# R107.net
KiCad netlist of a schematic drawn in EAGLE
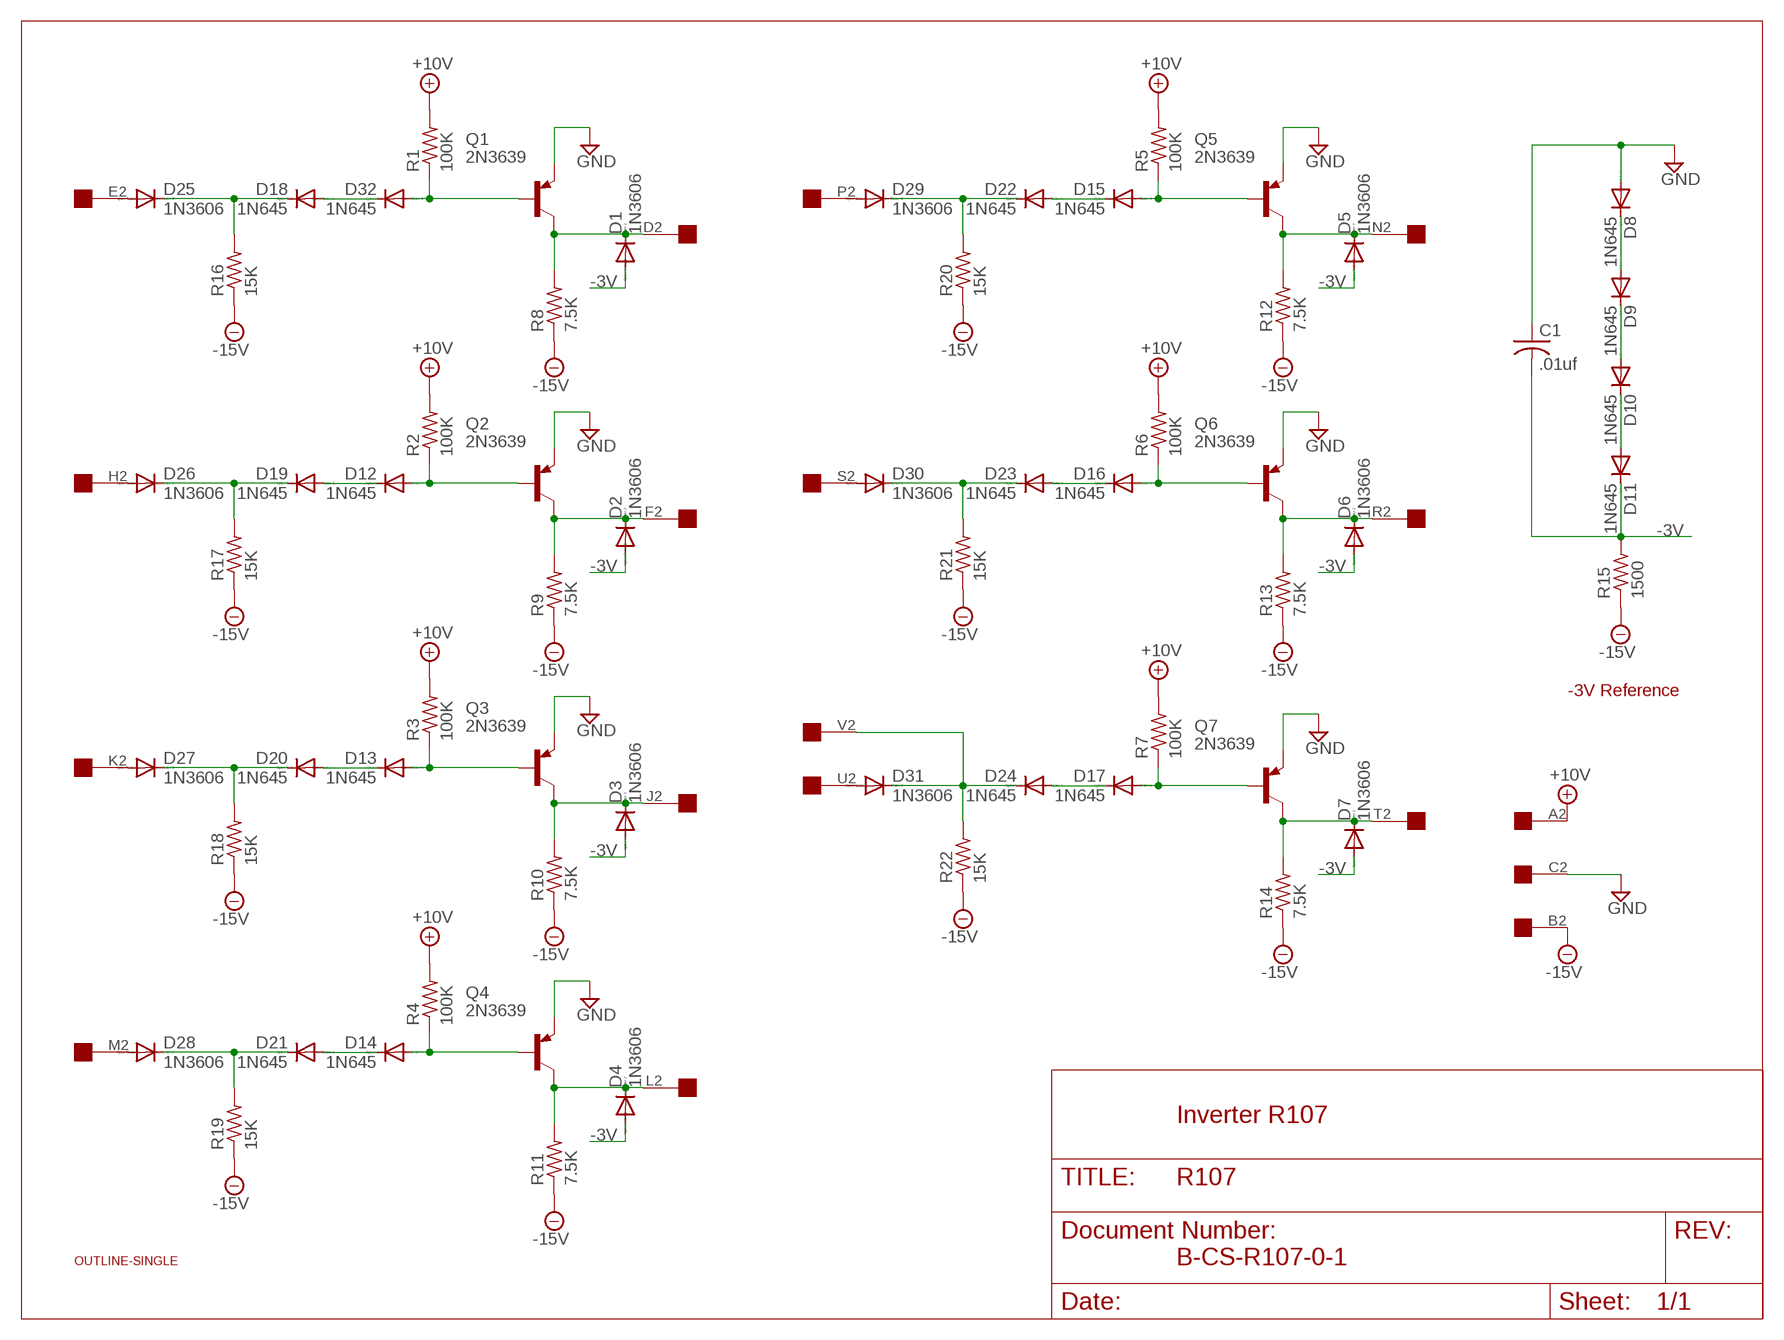
[diagram p0: schematic, sheet 1]

(export (version "E")
  (design (tool "Eeschema 10.0.6"))
  (components
    (comp (ref "C1")
      (value ".01uf")
      (footprint "eagle-import:C050-025X075")
      (libsource (lib "eagle-import") (part "C-US050-025X075"))
    )
    (comp (ref "D1")
      (value "1N3606")
      (footprint "eagle-import:DO35-10")
      (libsource (lib "eagle-import") (part "1N4148DO35-10"))
    )
    (comp (ref "D2")
      (value "1N3606")
      (footprint "eagle-import:DO35-10")
      (libsource (lib "eagle-import") (part "1N4148DO35-10"))
    )
    (comp (ref "D3")
      (value "1N3606")
      (footprint "eagle-import:DO35-10")
      (libsource (lib "eagle-import") (part "1N4148DO35-10"))
    )
    (comp (ref "D4")
      (value "1N3606")
      (footprint "eagle-import:DO35-10")
      (libsource (lib "eagle-import") (part "1N4148DO35-10"))
    )
    (comp (ref "D5")
      (value "1N3606")
      (footprint "eagle-import:DO35-10")
      (libsource (lib "eagle-import") (part "1N4148DO35-10"))
    )
    (comp (ref "D6")
      (value "1N3606")
      (footprint "eagle-import:DO35-10")
      (libsource (lib "eagle-import") (part "1N4148DO35-10"))
    )
    (comp (ref "D7")
      (value "1N3606")
      (footprint "eagle-import:DO35-10")
      (libsource (lib "eagle-import") (part "1N4148DO35-10"))
    )
    (comp (ref "D8")
      (value "1N645")
      (footprint "eagle-import:DO35-10")
      (libsource (lib "eagle-import") (part "1N4148DO35-10"))
    )
    (comp (ref "D9")
      (value "1N645")
      (footprint "eagle-import:DO35-10")
      (libsource (lib "eagle-import") (part "1N4148DO35-10"))
    )
    (comp (ref "D10")
      (value "1N645")
      (footprint "eagle-import:DO35-10")
      (libsource (lib "eagle-import") (part "1N4148DO35-10"))
    )
    (comp (ref "D11")
      (value "1N645")
      (footprint "eagle-import:DO35-10")
      (libsource (lib "eagle-import") (part "1N4148DO35-10"))
    )
    (comp (ref "D12")
      (value "1N645")
      (footprint "eagle-import:DO35-10")
      (libsource (lib "eagle-import") (part "1N4148DO35-10"))
    )
    (comp (ref "D13")
      (value "1N645")
      (footprint "eagle-import:DO35-10")
      (libsource (lib "eagle-import") (part "1N4148DO35-10"))
    )
    (comp (ref "D14")
      (value "1N645")
      (footprint "eagle-import:DO35-10")
      (libsource (lib "eagle-import") (part "1N4148DO35-10"))
    )
    (comp (ref "D15")
      (value "1N645")
      (footprint "eagle-import:DO35-10")
      (libsource (lib "eagle-import") (part "1N4148DO35-10"))
    )
    (comp (ref "D16")
      (value "1N645")
      (footprint "eagle-import:DO35-10")
      (libsource (lib "eagle-import") (part "1N4148DO35-10"))
    )
    (comp (ref "D17")
      (value "1N645")
      (footprint "eagle-import:DO35-10")
      (libsource (lib "eagle-import") (part "1N4148DO35-10"))
    )
    (comp (ref "D18")
      (value "1N645")
      (footprint "eagle-import:DO35-10")
      (libsource (lib "eagle-import") (part "1N4148DO35-10"))
    )
    (comp (ref "D19")
      (value "1N645")
      (footprint "eagle-import:DO35-10")
      (libsource (lib "eagle-import") (part "1N4148DO35-10"))
    )
    (comp (ref "D20")
      (value "1N645")
      (footprint "eagle-import:DO35-10")
      (libsource (lib "eagle-import") (part "1N4148DO35-10"))
    )
    (comp (ref "D21")
      (value "1N645")
      (footprint "eagle-import:DO35-10")
      (libsource (lib "eagle-import") (part "1N4148DO35-10"))
    )
    (comp (ref "D22")
      (value "1N645")
      (footprint "eagle-import:DO35-10")
      (libsource (lib "eagle-import") (part "1N4148DO35-10"))
    )
    (comp (ref "D23")
      (value "1N645")
      (footprint "eagle-import:DO35-10")
      (libsource (lib "eagle-import") (part "1N4148DO35-10"))
    )
    (comp (ref "D24")
      (value "1N645")
      (footprint "eagle-import:DO35-10")
      (libsource (lib "eagle-import") (part "1N4148DO35-10"))
    )
    (comp (ref "D25")
      (value "1N3606")
      (footprint "eagle-import:DO35-10")
      (libsource (lib "eagle-import") (part "1N4148DO35-10"))
    )
    (comp (ref "D26")
      (value "1N3606")
      (footprint "eagle-import:DO35-10")
      (libsource (lib "eagle-import") (part "1N4148DO35-10"))
    )
    (comp (ref "D27")
      (value "1N3606")
      (footprint "eagle-import:DO35-10")
      (libsource (lib "eagle-import") (part "1N4148DO35-10"))
    )
    (comp (ref "D28")
      (value "1N3606")
      (footprint "eagle-import:DO35-10")
      (libsource (lib "eagle-import") (part "1N4148DO35-10"))
    )
    (comp (ref "D29")
      (value "1N3606")
      (footprint "eagle-import:DO35-10")
      (libsource (lib "eagle-import") (part "1N4148DO35-10"))
    )
    (comp (ref "D30")
      (value "1N3606")
      (footprint "eagle-import:DO35-10")
      (libsource (lib "eagle-import") (part "1N4148DO35-10"))
    )
    (comp (ref "D31")
      (value "1N3606")
      (footprint "eagle-import:DO35-10")
      (libsource (lib "eagle-import") (part "1N4148DO35-10"))
    )
    (comp (ref "D32")
      (value "1N645")
      (footprint "eagle-import:DO35-10")
      (libsource (lib "eagle-import") (part "1N4148DO35-10"))
    )
    (comp (ref "Q1")
      (value "2N3639")
      (footprint "eagle-import:TO39")
      (libsource (lib "eagle-import") (part "2N3637"))
    )
    (comp (ref "Q2")
      (value "2N3639")
      (footprint "eagle-import:TO39")
      (libsource (lib "eagle-import") (part "2N3637"))
    )
    (comp (ref "Q3")
      (value "2N3639")
      (footprint "eagle-import:TO39")
      (libsource (lib "eagle-import") (part "2N3637"))
    )
    (comp (ref "Q4")
      (value "2N3639")
      (footprint "eagle-import:TO39")
      (libsource (lib "eagle-import") (part "2N3637"))
    )
    (comp (ref "Q5")
      (value "2N3639")
      (footprint "eagle-import:TO39")
      (libsource (lib "eagle-import") (part "2N3637"))
    )
    (comp (ref "Q6")
      (value "2N3639")
      (footprint "eagle-import:TO39")
      (libsource (lib "eagle-import") (part "2N3637"))
    )
    (comp (ref "Q7")
      (value "2N3639")
      (footprint "eagle-import:TO39")
      (libsource (lib "eagle-import") (part "2N3637"))
    )
    (comp (ref "R1")
      (value "100K")
      (footprint "eagle-import:0207_10")
      (libsource (lib "eagle-import") (part "R-US_0207/10"))
    )
    (comp (ref "R2")
      (value "100K")
      (footprint "eagle-import:0207_10")
      (libsource (lib "eagle-import") (part "R-US_0207/10"))
    )
    (comp (ref "R3")
      (value "100K")
      (footprint "eagle-import:0207_10")
      (libsource (lib "eagle-import") (part "R-US_0207/10"))
    )
    (comp (ref "R4")
      (value "100K")
      (footprint "eagle-import:0207_10")
      (libsource (lib "eagle-import") (part "R-US_0207/10"))
    )
    (comp (ref "R5")
      (value "100K")
      (footprint "eagle-import:0207_10")
      (libsource (lib "eagle-import") (part "R-US_0207/10"))
    )
    (comp (ref "R6")
      (value "100K")
      (footprint "eagle-import:0207_10")
      (libsource (lib "eagle-import") (part "R-US_0207/10"))
    )
    (comp (ref "R7")
      (value "100K")
      (footprint "eagle-import:0207_10")
      (libsource (lib "eagle-import") (part "R-US_0207/10"))
    )
    (comp (ref "R8")
      (value "7.5K")
      (footprint "eagle-import:0207_10")
      (libsource (lib "eagle-import") (part "R-US_0207/10"))
    )
    (comp (ref "R9")
      (value "7.5K")
      (footprint "eagle-import:0207_10")
      (libsource (lib "eagle-import") (part "R-US_0207/10"))
    )
    (comp (ref "R10")
      (value "7.5K")
      (footprint "eagle-import:0207_10")
      (libsource (lib "eagle-import") (part "R-US_0207/10"))
    )
    (comp (ref "R11")
      (value "7.5K")
      (footprint "eagle-import:0207_10")
      (libsource (lib "eagle-import") (part "R-US_0207/10"))
    )
    (comp (ref "R12")
      (value "7.5K")
      (footprint "eagle-import:0207_10")
      (libsource (lib "eagle-import") (part "R-US_0207/10"))
    )
    (comp (ref "R13")
      (value "7.5K")
      (footprint "eagle-import:0207_10")
      (libsource (lib "eagle-import") (part "R-US_0207/10"))
    )
    (comp (ref "R14")
      (value "7.5K")
      (footprint "eagle-import:0207_10")
      (libsource (lib "eagle-import") (part "R-US_0207/10"))
    )
    (comp (ref "R15")
      (value "1500")
      (footprint "eagle-import:0207_10")
      (libsource (lib "eagle-import") (part "R-US_0207/10"))
    )
    (comp (ref "R16")
      (value "15K")
      (footprint "eagle-import:0207_10")
      (libsource (lib "eagle-import") (part "R-US_0207/10"))
    )
    (comp (ref "R17")
      (value "15K")
      (footprint "eagle-import:0207_10")
      (libsource (lib "eagle-import") (part "R-US_0207/10"))
    )
    (comp (ref "R18")
      (value "15K")
      (footprint "eagle-import:0207_10")
      (libsource (lib "eagle-import") (part "R-US_0207/10"))
    )
    (comp (ref "R19")
      (value "15K")
      (footprint "eagle-import:0207_10")
      (libsource (lib "eagle-import") (part "R-US_0207/10"))
    )
    (comp (ref "R20")
      (value "15K")
      (footprint "eagle-import:0207_10")
      (libsource (lib "eagle-import") (part "R-US_0207/10"))
    )
    (comp (ref "R21")
      (value "15K")
      (footprint "eagle-import:0207_10")
      (libsource (lib "eagle-import") (part "R-US_0207/10"))
    )
    (comp (ref "R22")
      (value "15K")
      (footprint "eagle-import:0207_10")
      (libsource (lib "eagle-import") (part "R-US_0207/10"))
    )
    (comp (ref "U$1")
      (value "OUTLINE-SINGLE")
      (footprint "eagle-import:SINGLE")
      (libsource (lib "eagle-import") (part "OUTLINE-SINGLE"))
    )
    (comp (ref "U$2")
      (value "EDGE-1")
      (footprint "eagle-import:EDGE-CON1")
      (libsource (lib "eagle-import") (part "EDGE-1"))
    )
  )
  (nets
    (net (code "1") (name "+10V") (class "Default")
      (node (ref "R1") (pin "2") (pinfunction "2_2") (pintype "passive"))
      (node (ref "R2") (pin "2") (pinfunction "2_2") (pintype "passive"))
      (node (ref "R3") (pin "2") (pinfunction "2_2") (pintype "passive"))
      (node (ref "R4") (pin "2") (pinfunction "2_2") (pintype "passive"))
      (node (ref "R5") (pin "2") (pinfunction "2_2") (pintype "passive"))
      (node (ref "R6") (pin "2") (pinfunction "2_2") (pintype "passive"))
      (node (ref "R7") (pin "2") (pinfunction "2_2") (pintype "passive"))
      (node (ref "U$2") (pin "A2") (pinfunction "1_A2") (pintype "bidirectional"))
    )
    (net (code "2") (name "-15V") (class "Default")
      (node (ref "R10") (pin "1") (pinfunction "1_1") (pintype "passive"))
      (node (ref "R11") (pin "1") (pinfunction "1_1") (pintype "passive"))
      (node (ref "R12") (pin "1") (pinfunction "1_1") (pintype "passive"))
      (node (ref "R13") (pin "1") (pinfunction "1_1") (pintype "passive"))
      (node (ref "R14") (pin "1") (pinfunction "1_1") (pintype "passive"))
      (node (ref "R15") (pin "1") (pinfunction "1_1") (pintype "passive"))
      (node (ref "R16") (pin "1") (pinfunction "1_1") (pintype "passive"))
      (node (ref "R17") (pin "1") (pinfunction "1_1") (pintype "passive"))
      (node (ref "R18") (pin "1") (pinfunction "1_1") (pintype "passive"))
      (node (ref "R19") (pin "1") (pinfunction "1_1") (pintype "passive"))
      (node (ref "R20") (pin "1") (pinfunction "1_1") (pintype "passive"))
      (node (ref "R21") (pin "1") (pinfunction "1_1") (pintype "passive"))
      (node (ref "R22") (pin "1") (pinfunction "1_1") (pintype "passive"))
      (node (ref "R8") (pin "1") (pinfunction "1_1") (pintype "passive"))
      (node (ref "R9") (pin "1") (pinfunction "1_1") (pintype "passive"))
      (node (ref "U$2") (pin "B2") (pinfunction "1_B2") (pintype "bidirectional"))
    )
    (net (code "3") (name "/-3V") (class "Default")
      (node (ref "C1") (pin "2") (pinfunction "2_2") (pintype "passive"))
      (node (ref "D1") (pin "A") (pinfunction "A_A") (pintype "passive"))
      (node (ref "D11") (pin "C") (pinfunction "C_C") (pintype "passive"))
      (node (ref "D2") (pin "A") (pinfunction "A_A") (pintype "passive"))
      (node (ref "D3") (pin "A") (pinfunction "A_A") (pintype "passive"))
      (node (ref "D4") (pin "A") (pinfunction "A_A") (pintype "passive"))
      (node (ref "D5") (pin "A") (pinfunction "A_A") (pintype "passive"))
      (node (ref "D6") (pin "A") (pinfunction "A_A") (pintype "passive"))
      (node (ref "D7") (pin "A") (pinfunction "A_A") (pintype "passive"))
      (node (ref "R15") (pin "2") (pinfunction "2_2") (pintype "passive"))
    )
    (net (code "4") (name "GND") (class "Default")
      (node (ref "C1") (pin "1") (pinfunction "1_1") (pintype "passive"))
      (node (ref "D8") (pin "A") (pinfunction "A_A") (pintype "passive"))
      (node (ref "Q1") (pin "1") (pinfunction "E_1") (pintype "passive"))
      (node (ref "Q2") (pin "1") (pinfunction "E_1") (pintype "passive"))
      (node (ref "Q3") (pin "1") (pinfunction "E_1") (pintype "passive"))
      (node (ref "Q4") (pin "1") (pinfunction "E_1") (pintype "passive"))
      (node (ref "Q5") (pin "1") (pinfunction "E_1") (pintype "passive"))
      (node (ref "Q6") (pin "1") (pinfunction "E_1") (pintype "passive"))
      (node (ref "Q7") (pin "1") (pinfunction "E_1") (pintype "passive"))
      (node (ref "U$2") (pin "C2") (pinfunction "1_C2") (pintype "bidirectional"))
    )
    (net (code "5") (name "Net-(D8-PadC)") (class "Default")
      (node (ref "D8") (pin "C") (pinfunction "C_C") (pintype "passive"))
      (node (ref "D9") (pin "A") (pinfunction "A_A") (pintype "passive"))
    )
    (net (code "6") (name "Net-(D10-PadA)") (class "Default")
      (node (ref "D10") (pin "A") (pinfunction "A_A") (pintype "passive"))
      (node (ref "D9") (pin "C") (pinfunction "C_C") (pintype "passive"))
    )
    (net (code "7") (name "Net-(D10-PadC)") (class "Default")
      (node (ref "D10") (pin "C") (pinfunction "C_C") (pintype "passive"))
      (node (ref "D11") (pin "A") (pinfunction "A_A") (pintype "passive"))
    )
    (net (code "8") (name "Net-(D12-PadC)") (class "Default")
      (node (ref "D12") (pin "C") (pinfunction "C_C") (pintype "passive"))
      (node (ref "D19") (pin "A") (pinfunction "A_A") (pintype "passive"))
    )
    (net (code "9") (name "Net-(D13-PadC)") (class "Default")
      (node (ref "D13") (pin "C") (pinfunction "C_C") (pintype "passive"))
      (node (ref "D20") (pin "A") (pinfunction "A_A") (pintype "passive"))
    )
    (net (code "10") (name "Net-(D14-PadC)") (class "Default")
      (node (ref "D14") (pin "C") (pinfunction "C_C") (pintype "passive"))
      (node (ref "D21") (pin "A") (pinfunction "A_A") (pintype "passive"))
    )
    (net (code "11") (name "Net-(D15-PadC)") (class "Default")
      (node (ref "D15") (pin "C") (pinfunction "C_C") (pintype "passive"))
      (node (ref "D22") (pin "A") (pinfunction "A_A") (pintype "passive"))
    )
    (net (code "12") (name "Net-(D16-PadC)") (class "Default")
      (node (ref "D16") (pin "C") (pinfunction "C_C") (pintype "passive"))
      (node (ref "D23") (pin "A") (pinfunction "A_A") (pintype "passive"))
    )
    (net (code "13") (name "Net-(D17-PadC)") (class "Default")
      (node (ref "D17") (pin "C") (pinfunction "C_C") (pintype "passive"))
      (node (ref "D24") (pin "A") (pinfunction "A_A") (pintype "passive"))
    )
    (net (code "14") (name "Net-(D18-PadA)") (class "Default")
      (node (ref "D18") (pin "A") (pinfunction "A_A") (pintype "passive"))
      (node (ref "D32") (pin "C") (pinfunction "C_C") (pintype "passive"))
    )
    (net (code "15") (name "Net-(D18-PadC)") (class "Default")
      (node (ref "D18") (pin "C") (pinfunction "C_C") (pintype "passive"))
      (node (ref "D25") (pin "C") (pinfunction "C_C") (pintype "passive"))
      (node (ref "R16") (pin "2") (pinfunction "2_2") (pintype "passive"))
    )
    (net (code "16") (name "Net-(D19-PadC)") (class "Default")
      (node (ref "D19") (pin "C") (pinfunction "C_C") (pintype "passive"))
      (node (ref "D26") (pin "C") (pinfunction "C_C") (pintype "passive"))
      (node (ref "R17") (pin "2") (pinfunction "2_2") (pintype "passive"))
    )
    (net (code "17") (name "Net-(D20-PadC)") (class "Default")
      (node (ref "D20") (pin "C") (pinfunction "C_C") (pintype "passive"))
      (node (ref "D27") (pin "C") (pinfunction "C_C") (pintype "passive"))
      (node (ref "R18") (pin "2") (pinfunction "2_2") (pintype "passive"))
    )
    (net (code "18") (name "Net-(D21-PadC)") (class "Default")
      (node (ref "D21") (pin "C") (pinfunction "C_C") (pintype "passive"))
      (node (ref "D28") (pin "C") (pinfunction "C_C") (pintype "passive"))
      (node (ref "R19") (pin "2") (pinfunction "2_2") (pintype "passive"))
    )
    (net (code "19") (name "Net-(D22-PadC)") (class "Default")
      (node (ref "D22") (pin "C") (pinfunction "C_C") (pintype "passive"))
      (node (ref "D29") (pin "C") (pinfunction "C_C") (pintype "passive"))
      (node (ref "R20") (pin "2") (pinfunction "2_2") (pintype "passive"))
    )
    (net (code "20") (name "Net-(D23-PadC)") (class "Default")
      (node (ref "D23") (pin "C") (pinfunction "C_C") (pintype "passive"))
      (node (ref "D30") (pin "C") (pinfunction "C_C") (pintype "passive"))
      (node (ref "R21") (pin "2") (pinfunction "2_2") (pintype "passive"))
    )
    (net (code "21") (name "Net-(Q1-B)") (class "Default")
      (node (ref "D32") (pin "A") (pinfunction "A_A") (pintype "passive"))
      (node (ref "Q1") (pin "2") (pinfunction "B_2") (pintype "passive"))
      (node (ref "R1") (pin "1") (pinfunction "1_1") (pintype "passive"))
    )
    (net (code "22") (name "Net-(Q1-C)") (class "Default")
      (node (ref "D1") (pin "C") (pinfunction "C_C") (pintype "passive"))
      (node (ref "Q1") (pin "3") (pinfunction "C_3") (pintype "passive"))
      (node (ref "R8") (pin "2") (pinfunction "2_2") (pintype "passive"))
      (node (ref "U$2") (pin "D2") (pinfunction "1_D2") (pintype "bidirectional"))
    )
    (net (code "23") (name "Net-(Q2-B)") (class "Default")
      (node (ref "D12") (pin "A") (pinfunction "A_A") (pintype "passive"))
      (node (ref "Q2") (pin "2") (pinfunction "B_2") (pintype "passive"))
      (node (ref "R2") (pin "1") (pinfunction "1_1") (pintype "passive"))
    )
    (net (code "24") (name "Net-(Q2-C)") (class "Default")
      (node (ref "D2") (pin "C") (pinfunction "C_C") (pintype "passive"))
      (node (ref "Q2") (pin "3") (pinfunction "C_3") (pintype "passive"))
      (node (ref "R9") (pin "2") (pinfunction "2_2") (pintype "passive"))
      (node (ref "U$2") (pin "F2") (pinfunction "1_F2") (pintype "bidirectional"))
    )
    (net (code "25") (name "Net-(Q3-B)") (class "Default")
      (node (ref "D13") (pin "A") (pinfunction "A_A") (pintype "passive"))
      (node (ref "Q3") (pin "2") (pinfunction "B_2") (pintype "passive"))
      (node (ref "R3") (pin "1") (pinfunction "1_1") (pintype "passive"))
    )
    (net (code "26") (name "Net-(Q3-C)") (class "Default")
      (node (ref "D3") (pin "C") (pinfunction "C_C") (pintype "passive"))
      (node (ref "Q3") (pin "3") (pinfunction "C_3") (pintype "passive"))
      (node (ref "R10") (pin "2") (pinfunction "2_2") (pintype "passive"))
      (node (ref "U$2") (pin "J2") (pinfunction "1_J2") (pintype "bidirectional"))
    )
    (net (code "27") (name "Net-(Q4-B)") (class "Default")
      (node (ref "D14") (pin "A") (pinfunction "A_A") (pintype "passive"))
      (node (ref "Q4") (pin "2") (pinfunction "B_2") (pintype "passive"))
      (node (ref "R4") (pin "1") (pinfunction "1_1") (pintype "passive"))
    )
    (net (code "28") (name "Net-(Q4-C)") (class "Default")
      (node (ref "D4") (pin "C") (pinfunction "C_C") (pintype "passive"))
      (node (ref "Q4") (pin "3") (pinfunction "C_3") (pintype "passive"))
      (node (ref "R11") (pin "2") (pinfunction "2_2") (pintype "passive"))
      (node (ref "U$2") (pin "L2") (pinfunction "1_L2") (pintype "bidirectional"))
    )
    (net (code "29") (name "Net-(Q5-B)") (class "Default")
      (node (ref "D15") (pin "A") (pinfunction "A_A") (pintype "passive"))
      (node (ref "Q5") (pin "2") (pinfunction "B_2") (pintype "passive"))
      (node (ref "R5") (pin "1") (pinfunction "1_1") (pintype "passive"))
    )
    (net (code "30") (name "Net-(Q5-C)") (class "Default")
      (node (ref "D5") (pin "C") (pinfunction "C_C") (pintype "passive"))
      (node (ref "Q5") (pin "3") (pinfunction "C_3") (pintype "passive"))
      (node (ref "R12") (pin "2") (pinfunction "2_2") (pintype "passive"))
      (node (ref "U$2") (pin "N2") (pinfunction "1_N2") (pintype "bidirectional"))
    )
    (net (code "31") (name "Net-(Q6-B)") (class "Default")
      (node (ref "D16") (pin "A") (pinfunction "A_A") (pintype "passive"))
      (node (ref "Q6") (pin "2") (pinfunction "B_2") (pintype "passive"))
      (node (ref "R6") (pin "1") (pinfunction "1_1") (pintype "passive"))
    )
    (net (code "32") (name "Net-(Q6-C)") (class "Default")
      (node (ref "D6") (pin "C") (pinfunction "C_C") (pintype "passive"))
      (node (ref "Q6") (pin "3") (pinfunction "C_3") (pintype "passive"))
      (node (ref "R13") (pin "2") (pinfunction "2_2") (pintype "passive"))
      (node (ref "U$2") (pin "R2") (pinfunction "1_R2") (pintype "bidirectional"))
    )
    (net (code "33") (name "Net-(Q7-B)") (class "Default")
      (node (ref "D17") (pin "A") (pinfunction "A_A") (pintype "passive"))
      (node (ref "Q7") (pin "2") (pinfunction "B_2") (pintype "passive"))
      (node (ref "R7") (pin "1") (pinfunction "1_1") (pintype "passive"))
    )
    (net (code "34") (name "Net-(Q7-C)") (class "Default")
      (node (ref "D7") (pin "C") (pinfunction "C_C") (pintype "passive"))
      (node (ref "Q7") (pin "3") (pinfunction "C_3") (pintype "passive"))
      (node (ref "R14") (pin "2") (pinfunction "2_2") (pintype "passive"))
      (node (ref "U$2") (pin "T2") (pinfunction "1_T2") (pintype "bidirectional"))
    )
    (net (code "35") (name "Net-(U$2E-1)") (class "Default")
      (node (ref "D25") (pin "A") (pinfunction "A_A") (pintype "passive"))
      (node (ref "U$2") (pin "E2") (pinfunction "1_E2") (pintype "bidirectional"))
    )
    (net (code "36") (name "Net-(U$2G-1)") (class "Default")
      (node (ref "D26") (pin "A") (pinfunction "A_A") (pintype "passive"))
      (node (ref "U$2") (pin "H2") (pinfunction "1_H2") (pintype "bidirectional"))
    )
    (net (code "37") (name "Net-(U$2I-1)") (class "Default")
      (node (ref "D27") (pin "A") (pinfunction "A_A") (pintype "passive"))
      (node (ref "U$2") (pin "K2") (pinfunction "1_K2") (pintype "bidirectional"))
    )
    (net (code "38") (name "Net-(U$2K-1)") (class "Default")
      (node (ref "D28") (pin "A") (pinfunction "A_A") (pintype "passive"))
      (node (ref "U$2") (pin "M2") (pinfunction "1_M2") (pintype "bidirectional"))
    )
    (net (code "39") (name "Net-(U$2M-1)") (class "Default")
      (node (ref "D29") (pin "A") (pinfunction "A_A") (pintype "passive"))
      (node (ref "U$2") (pin "P2") (pinfunction "1_P2") (pintype "bidirectional"))
    )
    (net (code "40") (name "Net-(U$2O-1)") (class "Default")
      (node (ref "D30") (pin "A") (pinfunction "A_A") (pintype "passive"))
      (node (ref "U$2") (pin "S2") (pinfunction "1_S2") (pintype "bidirectional"))
    )
    (net (code "41") (name "Net-(U$2Q-1)") (class "Default")
      (node (ref "D31") (pin "A") (pinfunction "A_A") (pintype "passive"))
      (node (ref "U$2") (pin "U2") (pinfunction "1_U2") (pintype "bidirectional"))
    )
    (net (code "42") (name "Net-(U$2R-1)") (class "Default")
      (node (ref "D24") (pin "C") (pinfunction "C_C") (pintype "passive"))
      (node (ref "D31") (pin "C") (pinfunction "C_C") (pintype "passive"))
      (node (ref "R22") (pin "2") (pinfunction "2_2") (pintype "passive"))
      (node (ref "U$2") (pin "V2") (pinfunction "1_V2") (pintype "bidirectional"))
    )
  )
)
